# MCU.net
KiCad netlist of a schematic drawn in Altium Designer
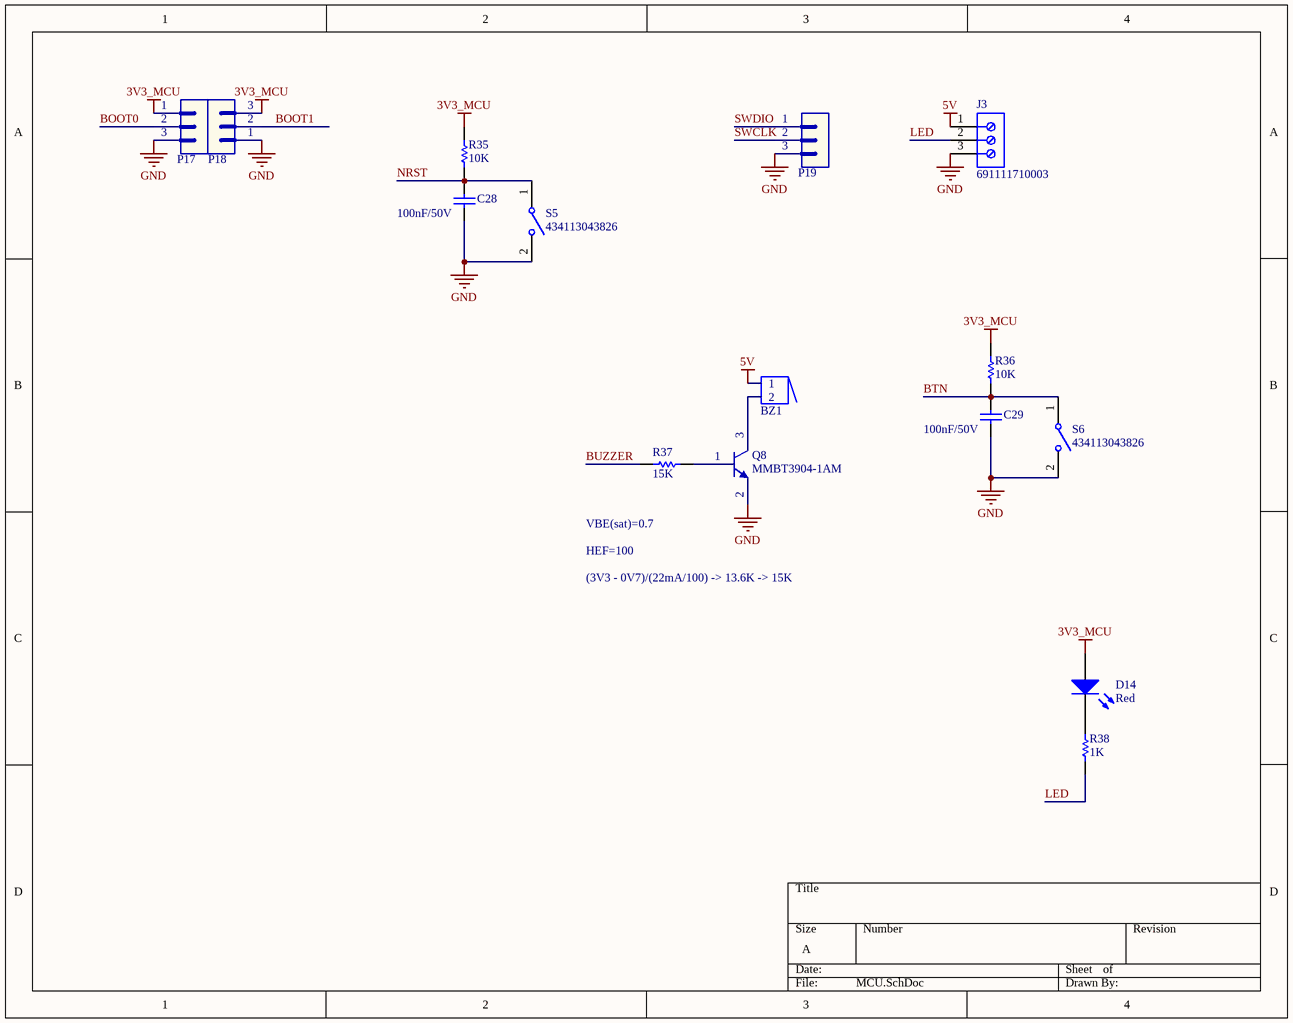
[diagram p0: MCU.SchDoc]

(export (version "E")
  (design (tool "Eeschema 10.0.6"))
  (components
    (comp (ref "BZ1") (value "Buzzer") (footprint "BUZZER") (libsource (lib "PIF_C16_lib") (part "Buzzer")))
    (comp (ref "C28")
      (value "100nF/50V")
      (footprint "CAP-SM-0805")
      (description "CAP CER 0.1UF 50V Y5V 0805")
      (fields
        (field (name "MANUFACTURER") "Samsung Electro-Mechanics")
        (field (name "MANUFACTURER PART NUMBER") "CL21F104ZBCNNNC")
      )
      (libsource (lib "Capacitor") (part "Cap-100nF-50V-0805"))
    )
    (comp (ref "C29")
      (value "100nF/50V")
      (footprint "CAP-SM-0805")
      (description "CAP CER 0.1UF 50V Y5V 0805")
      (fields
        (field (name "MANUFACTURER") "Samsung Electro-Mechanics")
        (field (name "MANUFACTURER PART NUMBER") "CL21F104ZBCNNNC")
      )
      (libsource (lib "Capacitor") (part "Cap-100nF-50V-0805"))
    )
    (comp (ref "D14")
      (value "Red")
      (footprint "LED-3mm")
      (description "LED RED CLEAR T-1 T/H")
      (fields
        (field (name "MANUFACTURER") "Kingbright")
        (field (name "MANUFACTURER PART NUMBER") "WP710A10SEC/J3")
      )
      (libsource (lib "LED") (part "LED-RED-TH-3mm"))
    )
    (comp (ref "J3")
      (value "691111710003")
      (footprint "691111710003")
      (description "WR-TBL Serie 111 Horizontal Entry Modular, Pressure Clamp, pitch 5mm, 3p")
      (fields (field (name "PUBLISHER") "Wurth Elektronik"))
      (libsource (lib "691322310002_Altium_WR-TBL_rev19a") (part "691111710003"))
    )
    (comp (ref "P17")
      (value "Header 3")
      (footprint "JP3")
      (description "Header, 3-Pin")
      (fields (field (name "PUBLISHER") "Altium Limited"))
      (libsource (lib "Header-Connector") (part "Header 3"))
    )
    (comp (ref "P18")
      (value "Header 3")
      (footprint "JP3")
      (description "Header, 3-Pin")
      (fields (field (name "PUBLISHER") "Altium Limited"))
      (libsource (lib "") (part "Header 3_1"))
    )
    (comp (ref "P19")
      (value "Header 3")
      (footprint "JP3")
      (description "Header, 3-Pin")
      (fields (field (name "PUBLISHER") "Altium Limited"))
      (libsource (lib "Header-Connector") (part "Header 3"))
    )
    (comp (ref "Q8")
      (value "MMBT3904-1AM")
      (footprint "SOT23_NEX")
      (libsource (lib "BJT") (part "MMBT3904-1AM"))
    )
    (comp (ref "R35")
      (value "10K")
      (footprint "Resistor:RES-SM-0805")
      (description "RES 10K OHM 1% 1/4W 0805")
      (fields
        (field (name "MANUFACTURER") "Stackpole Electronics Inc")
        (field (name "MANUFACTURER PART NUMBER") "RNCP0805FTD10K0")
      )
      (libsource (lib "Resistor") (part "Res-10k-0805"))
    )
    (comp (ref "R36")
      (value "10K")
      (footprint "Resistor:RES-SM-0805")
      (description "RES 10K OHM 1% 1/4W 0805")
      (fields
        (field (name "MANUFACTURER") "Stackpole Electronics Inc")
        (field (name "MANUFACTURER PART NUMBER") "RNCP0805FTD10K0")
      )
      (libsource (lib "Resistor") (part "Res-10k-0805"))
    )
    (comp (ref "R37")
      (value "15K")
      (footprint "Resistor:RES-SM-0805")
      (description "RES 15K OHM 1% 1/4W 0805")
      (fields
        (field (name "MANUFACTURER") "TE Connectivity Passive Product")
        (field (name "MANUFACTURER PART NUMBER") "CRGCQ0805F15K")
      )
      (libsource (lib "Resistor") (part "Res-15K-0805"))
    )
    (comp (ref "R38")
      (value "1K")
      (footprint "Resistor:RES-SM-0805")
      (description "RES 1K OHM 1% 1/4W 0805")
      (fields
        (field (name "MANUFACTURER") "Stackpole Electronics Inc")
        (field (name "MANUFACTURER PART NUMBER") "RNCP0805FTD1K00")
      )
      (libsource (lib "Resistor") (part "Res-1K-0805"))
    )
    (comp (ref "S5")
      (value "434113043826")
      (footprint "434113043826")
      (description "WS-TASV J-Bend SMT Tact Switch 6x3.5mm, height 4.3mm, 260gf")
      (fields (field (name "PUBLISHER") "Wurth Elektronik"))
      (libsource (lib "434113043826_Altium_WS-TASV_rev20a") (part "434113043826"))
    )
    (comp (ref "S6")
      (value "434113043826")
      (footprint "434113043826")
      (description "WS-TASV J-Bend SMT Tact Switch 6x3.5mm, height 4.3mm, 260gf")
      (fields (field (name "PUBLISHER") "Wurth Elektronik"))
      (libsource (lib "434113043826_Altium_WS-TASV_rev20a") (part "434113043826"))
    )
  )
  (nets
    (net (code "1") (name "/BOOT0") (class "Default")
      (node (ref "P17") (pin "2") (pinfunction "2_2") (pintype "passive"))
    )
    (net (code "2") (name "/BOOT1") (class "Default")
      (node (ref "P18") (pin "2") (pinfunction "2_2") (pintype "passive"))
    )
    (net (code "3") (name "/BTN") (class "Default")
      (node (ref "C29") (pin "2") (pinfunction "2_2") (pintype "passive"))
      (node (ref "R36") (pin "2") (pinfunction "2_2") (pintype "passive"))
      (node (ref "S6") (pin "1") (pinfunction "1_1") (pintype "passive"))
    )
    (net (code "4") (name "/BUZZER") (class "Default")
      (node (ref "R37") (pin "1") (pinfunction "1_1") (pintype "passive"))
    )
    (net (code "5") (name "/LED") (class "Default")
      (node (ref "J3") (pin "2") (pinfunction "2_2") (pintype "passive"))
      (node (ref "R38") (pin "1") (pinfunction "1_1") (pintype "passive"))
    )
    (net (code "6") (name "/NRST") (class "Default")
      (node (ref "C28") (pin "2") (pinfunction "2_2") (pintype "passive"))
      (node (ref "R35") (pin "2") (pinfunction "2_2") (pintype "passive"))
      (node (ref "S5") (pin "1") (pinfunction "1_1") (pintype "passive"))
    )
    (net (code "7") (name "/SWCLK") (class "Default")
      (node (ref "P19") (pin "2") (pinfunction "2_2") (pintype "passive"))
    )
    (net (code "8") (name "/SWDIO") (class "Default")
      (node (ref "P19") (pin "1") (pinfunction "1_1") (pintype "passive"))
    )
    (net (code "9") (name "3V3_MCU") (class "Default")
      (node (ref "D14") (pin "1") (pinfunction "A_1") (pintype "passive"))
      (node (ref "P17") (pin "1") (pinfunction "1_1") (pintype "passive"))
      (node (ref "P18") (pin "3") (pinfunction "3_3") (pintype "passive"))
      (node (ref "R35") (pin "1") (pinfunction "1_1") (pintype "passive"))
      (node (ref "R36") (pin "1") (pinfunction "1_1") (pintype "passive"))
    )
    (net (code "10") (name "5V") (class "Default")
      (node (ref "BZ1") (pin "1") (pinfunction "1_1") (pintype "passive"))
      (node (ref "J3") (pin "1") (pinfunction "1_1") (pintype "passive"))
    )
    (net (code "11") (name "GND") (class "Default")
      (node (ref "C28") (pin "1") (pinfunction "1_1") (pintype "passive"))
      (node (ref "C29") (pin "1") (pinfunction "1_1") (pintype "passive"))
      (node (ref "J3") (pin "3") (pinfunction "3_3") (pintype "passive"))
      (node (ref "P17") (pin "3") (pinfunction "3_3") (pintype "passive"))
      (node (ref "P18") (pin "1") (pinfunction "1_1") (pintype "passive"))
      (node (ref "P19") (pin "3") (pinfunction "3_3") (pintype "passive"))
      (node (ref "Q8") (pin "2") (pinfunction "E_2") (pintype "passive"))
      (node (ref "S5") (pin "2") (pinfunction "2_2") (pintype "passive"))
      (node (ref "S6") (pin "2") (pinfunction "2_2") (pintype "passive"))
    )
    (net (code "12") (name "Net-(D14-K)") (class "Default")
      (node (ref "D14") (pin "2") (pinfunction "K_2") (pintype "passive"))
      (node (ref "R38") (pin "2") (pinfunction "2_2") (pintype "passive"))
    )
    (net (code "13") (name "Net-(Q8-B)") (class "Default")
      (node (ref "Q8") (pin "1") (pinfunction "B_1") (pintype "passive"))
      (node (ref "R37") (pin "2") (pinfunction "2_2") (pintype "passive"))
    )
    (net (code "14") (name "Net-(Q8-C)") (class "Default")
      (node (ref "BZ1") (pin "2") (pinfunction "2_2") (pintype "passive"))
      (node (ref "Q8") (pin "3") (pinfunction "C_3") (pintype "passive"))
    )
  )
)
